# 02_CONNECTION.net
KiCad netlist of a schematic drawn in Altium Designer
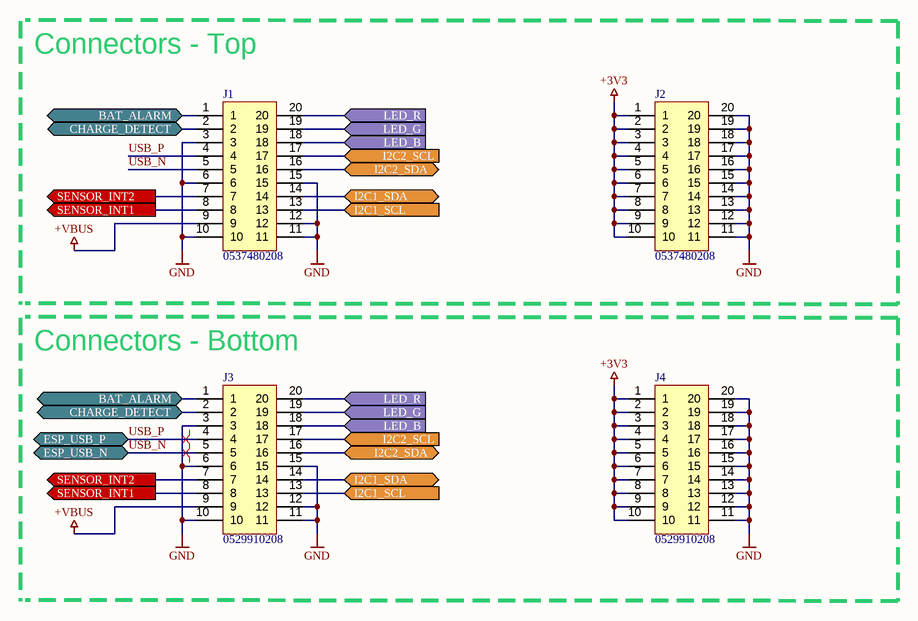
[diagram p0: 02 CONNECTION.SchDoc]

(export (version "E")
  (design (tool "Eeschema 10.0.6"))
  (components
    (comp (ref "J1")
      (value "0537480208")
      (footprint "0537480208")
      (description "CONN PLUG 20POS SMD GOLD")
      (fields (field (name "MANUFACTURER") "MOLEX"))
      (libsource (lib "altium_symbol") (part "0537480208"))
    )
    (comp (ref "J2")
      (value "0537480208")
      (footprint "0537480208")
      (description "CONN PLUG 20POS SMD GOLD")
      (fields (field (name "MANUFACTURER") "MOLEX"))
      (libsource (lib "altium_symbol") (part "0537480208"))
    )
    (comp (ref "J3")
      (value "0529910208")
      (footprint "0529910208")
      (description "CONN PLUG 20POS SMD GOLD")
      (fields (field (name "MANUFACTURER") "MOLEX"))
      (libsource (lib "altium_symbol") (part "0529910208"))
    )
    (comp (ref "J4")
      (value "0529910208")
      (footprint "0529910208")
      (description "CONN PLUG 20POS SMD GOLD")
      (fields (field (name "MANUFACTURER") "MOLEX"))
      (libsource (lib "altium_symbol") (part "0529910208"))
    )
  )
  (nets
    (net (code "1") (name "+3V3") (class "Default")
      (node (ref "J2") (pin "1") (pinfunction "1_1") (pintype "passive"))
      (node (ref "J2") (pin "10") (pinfunction "10_10") (pintype "passive"))
      (node (ref "J2") (pin "2") (pinfunction "2_2") (pintype "passive"))
      (node (ref "J2") (pin "3") (pinfunction "3_3") (pintype "passive"))
      (node (ref "J2") (pin "4") (pinfunction "4_4") (pintype "passive"))
      (node (ref "J2") (pin "5") (pinfunction "5_5") (pintype "passive"))
      (node (ref "J2") (pin "6") (pinfunction "6_6") (pintype "passive"))
      (node (ref "J2") (pin "7") (pinfunction "7_7") (pintype "passive"))
      (node (ref "J2") (pin "8") (pinfunction "8_8") (pintype "passive"))
      (node (ref "J2") (pin "9") (pinfunction "9_9") (pintype "passive"))
      (node (ref "J4") (pin "1") (pinfunction "1_1") (pintype "passive"))
      (node (ref "J4") (pin "10") (pinfunction "10_10") (pintype "passive"))
      (node (ref "J4") (pin "2") (pinfunction "2_2") (pintype "passive"))
      (node (ref "J4") (pin "3") (pinfunction "3_3") (pintype "passive"))
      (node (ref "J4") (pin "4") (pinfunction "4_4") (pintype "passive"))
      (node (ref "J4") (pin "5") (pinfunction "5_5") (pintype "passive"))
      (node (ref "J4") (pin "6") (pinfunction "6_6") (pintype "passive"))
      (node (ref "J4") (pin "7") (pinfunction "7_7") (pintype "passive"))
      (node (ref "J4") (pin "8") (pinfunction "8_8") (pintype "passive"))
      (node (ref "J4") (pin "9") (pinfunction "9_9") (pintype "passive"))
    )
    (net (code "2") (name "+VBUS") (class "Default")
      (node (ref "J1") (pin "9") (pinfunction "9_9") (pintype "passive"))
      (node (ref "J3") (pin "9") (pinfunction "9_9") (pintype "passive"))
    )
    (net (code "3") (name "/BAT_ALARM") (class "Default")
      (node (ref "J1") (pin "1") (pinfunction "1_1") (pintype "passive"))
      (node (ref "J3") (pin "1") (pinfunction "1_1") (pintype "passive"))
    )
    (net (code "4") (name "/CHARGE_DETECT") (class "Default")
      (node (ref "J1") (pin "2") (pinfunction "2_2") (pintype "passive"))
      (node (ref "J3") (pin "2") (pinfunction "2_2") (pintype "passive"))
    )
    (net (code "5") (name "/I2C1_SCL") (class "Default")
      (node (ref "J1") (pin "13") (pinfunction "13_13") (pintype "passive"))
      (node (ref "J3") (pin "13") (pinfunction "13_13") (pintype "passive"))
    )
    (net (code "6") (name "/I2C1_SDA") (class "Default")
      (node (ref "J1") (pin "14") (pinfunction "14_14") (pintype "passive"))
      (node (ref "J3") (pin "14") (pinfunction "14_14") (pintype "passive"))
    )
    (net (code "7") (name "/I2C2_SCL") (class "Default")
      (node (ref "J1") (pin "17") (pinfunction "17_17") (pintype "passive"))
      (node (ref "J3") (pin "17") (pinfunction "17_17") (pintype "passive"))
    )
    (net (code "8") (name "/I2C2_SDA") (class "Default")
      (node (ref "J1") (pin "16") (pinfunction "16_16") (pintype "passive"))
      (node (ref "J3") (pin "16") (pinfunction "16_16") (pintype "passive"))
    )
    (net (code "9") (name "/LED_B") (class "Default")
      (node (ref "J1") (pin "18") (pinfunction "18_18") (pintype "passive"))
      (node (ref "J3") (pin "18") (pinfunction "18_18") (pintype "passive"))
    )
    (net (code "10") (name "/LED_G") (class "Default")
      (node (ref "J1") (pin "19") (pinfunction "19_19") (pintype "passive"))
      (node (ref "J3") (pin "19") (pinfunction "19_19") (pintype "passive"))
    )
    (net (code "11") (name "/LED_R") (class "Default")
      (node (ref "J1") (pin "20") (pinfunction "20_20") (pintype "passive"))
      (node (ref "J3") (pin "20") (pinfunction "20_20") (pintype "passive"))
    )
    (net (code "12") (name "/SENSOR_INT1") (class "Default")
      (node (ref "J1") (pin "8") (pinfunction "8_8") (pintype "passive"))
      (node (ref "J3") (pin "8") (pinfunction "8_8") (pintype "passive"))
    )
    (net (code "13") (name "/SENSOR_INT2") (class "Default")
      (node (ref "J1") (pin "7") (pinfunction "7_7") (pintype "passive"))
      (node (ref "J3") (pin "7") (pinfunction "7_7") (pintype "passive"))
    )
    (net (code "14") (name "/USB_N") (class "Default")
      (node (ref "J1") (pin "5") (pinfunction "5_5") (pintype "passive"))
      (node (ref "J3") (pin "5") (pinfunction "5_5") (pintype "passive"))
    )
    (net (code "15") (name "/USB_P") (class "Default")
      (node (ref "J1") (pin "4") (pinfunction "4_4") (pintype "passive"))
      (node (ref "J3") (pin "4") (pinfunction "4_4") (pintype "passive"))
    )
    (net (code "16") (name "GND") (class "Default")
      (node (ref "J1") (pin "10") (pinfunction "10_10") (pintype "passive"))
      (node (ref "J1") (pin "11") (pinfunction "11_11") (pintype "passive"))
      (node (ref "J1") (pin "12") (pinfunction "12_12") (pintype "passive"))
      (node (ref "J1") (pin "15") (pinfunction "15_15") (pintype "passive"))
      (node (ref "J1") (pin "3") (pinfunction "3_3") (pintype "passive"))
      (node (ref "J1") (pin "6") (pinfunction "6_6") (pintype "passive"))
      (node (ref "J2") (pin "11") (pinfunction "11_11") (pintype "passive"))
      (node (ref "J2") (pin "12") (pinfunction "12_12") (pintype "passive"))
      (node (ref "J2") (pin "13") (pinfunction "13_13") (pintype "passive"))
      (node (ref "J2") (pin "14") (pinfunction "14_14") (pintype "passive"))
      (node (ref "J2") (pin "15") (pinfunction "15_15") (pintype "passive"))
      (node (ref "J2") (pin "16") (pinfunction "16_16") (pintype "passive"))
      (node (ref "J2") (pin "17") (pinfunction "17_17") (pintype "passive"))
      (node (ref "J2") (pin "18") (pinfunction "18_18") (pintype "passive"))
      (node (ref "J2") (pin "19") (pinfunction "19_19") (pintype "passive"))
      (node (ref "J2") (pin "20") (pinfunction "20_20") (pintype "passive"))
      (node (ref "J3") (pin "10") (pinfunction "10_10") (pintype "passive"))
      (node (ref "J3") (pin "11") (pinfunction "11_11") (pintype "passive"))
      (node (ref "J3") (pin "12") (pinfunction "12_12") (pintype "passive"))
      (node (ref "J3") (pin "15") (pinfunction "15_15") (pintype "passive"))
      (node (ref "J3") (pin "3") (pinfunction "3_3") (pintype "passive"))
      (node (ref "J3") (pin "6") (pinfunction "6_6") (pintype "passive"))
      (node (ref "J4") (pin "11") (pinfunction "11_11") (pintype "passive"))
      (node (ref "J4") (pin "12") (pinfunction "12_12") (pintype "passive"))
      (node (ref "J4") (pin "13") (pinfunction "13_13") (pintype "passive"))
      (node (ref "J4") (pin "14") (pinfunction "14_14") (pintype "passive"))
      (node (ref "J4") (pin "15") (pinfunction "15_15") (pintype "passive"))
      (node (ref "J4") (pin "16") (pinfunction "16_16") (pintype "passive"))
      (node (ref "J4") (pin "17") (pinfunction "17_17") (pintype "passive"))
      (node (ref "J4") (pin "18") (pinfunction "18_18") (pintype "passive"))
      (node (ref "J4") (pin "19") (pinfunction "19_19") (pintype "passive"))
      (node (ref "J4") (pin "20") (pinfunction "20_20") (pintype "passive"))
    )
  )
)
